# LED_Knihovna.net
KiCad netlist of a schematic drawn in EAGLE
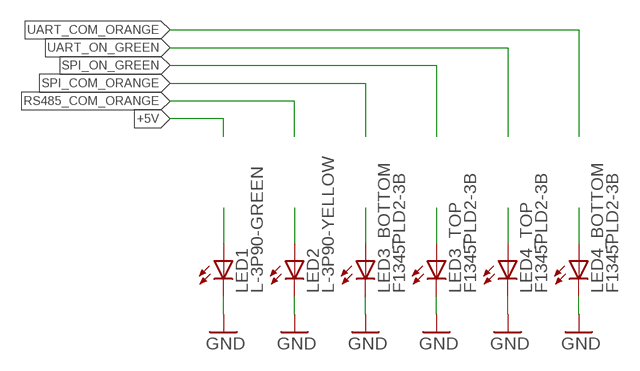
[diagram p0: schematic, sheet 1]

(export (version "E")
  (design (tool "Eeschema 10.0.6"))
  (components
    (comp (ref "LED1")
      (value "L-3P90-GREEN")
      (footprint "eagle-import:L-3P90")
      (libsource (lib "eagle-import") (part "L-3P90-GREEN"))
    )
    (comp (ref "LED2")
      (value "L-3P90-YELLOW")
      (footprint "eagle-import:L-3P90")
      (libsource (lib "eagle-import") (part "L-3P90-YELLOW"))
    )
    (comp (ref "LED3")
      (value "F1345PLD2-3B")
      (footprint "eagle-import:F1345PLD2-3B")
      (libsource (lib "eagle-import") (part "F1345PLD2-3B"))
    )
    (comp (ref "LED4")
      (value "F1345PLD2-3B")
      (footprint "eagle-import:F1345PLD2-3B")
      (libsource (lib "eagle-import") (part "F1345PLD2-3B"))
    )
  )
  (nets
    (net (code "2") (name "GND") (class "Default")
      (node (ref "LED1") (pin "K") (pinfunction "C_K") (pintype "passive"))
      (node (ref "LED2") (pin "K") (pinfunction "C_K") (pintype "passive"))
      (node (ref "LED3") (pin "1K") (pinfunction "C_1K") (pintype "passive"))
      (node (ref "LED3") (pin "2K") (pinfunction "C_2K") (pintype "passive"))
      (node (ref "LED4") (pin "1K") (pinfunction "C_1K") (pintype "passive"))
      (node (ref "LED4") (pin "2K") (pinfunction "C_2K") (pintype "passive"))
    )
    (net (code "8") (name "unconnected-(LED1-PadA)") (class "Default")
      (node (ref "LED1") (pin "A") (pinfunction "A_A") (pintype "passive"))
    )
    (net (code "9") (name "unconnected-(LED2-PadA)") (class "Default")
      (node (ref "LED2") (pin "A") (pinfunction "A_A") (pintype "passive"))
    )
    (net (code "10") (name "unconnected-(LED3A-A-Pad1A)") (class "Default")
      (node (ref "LED3") (pin "1A") (pinfunction "A_1A") (pintype "passive"))
    )
    (net (code "11") (name "unconnected-(LED3B-A-Pad2A)") (class "Default")
      (node (ref "LED3") (pin "2A") (pinfunction "A_2A") (pintype "passive"))
    )
    (net (code "12") (name "unconnected-(LED4A-A-Pad1A)") (class "Default")
      (node (ref "LED4") (pin "1A") (pinfunction "A_1A") (pintype "passive"))
    )
    (net (code "13") (name "unconnected-(LED4B-A-Pad2A)") (class "Default")
      (node (ref "LED4") (pin "2A") (pinfunction "A_2A") (pintype "passive"))
    )
  )
)
